# Tweetronic_Base.net
KiCad netlist of a schematic drawn in EAGLE
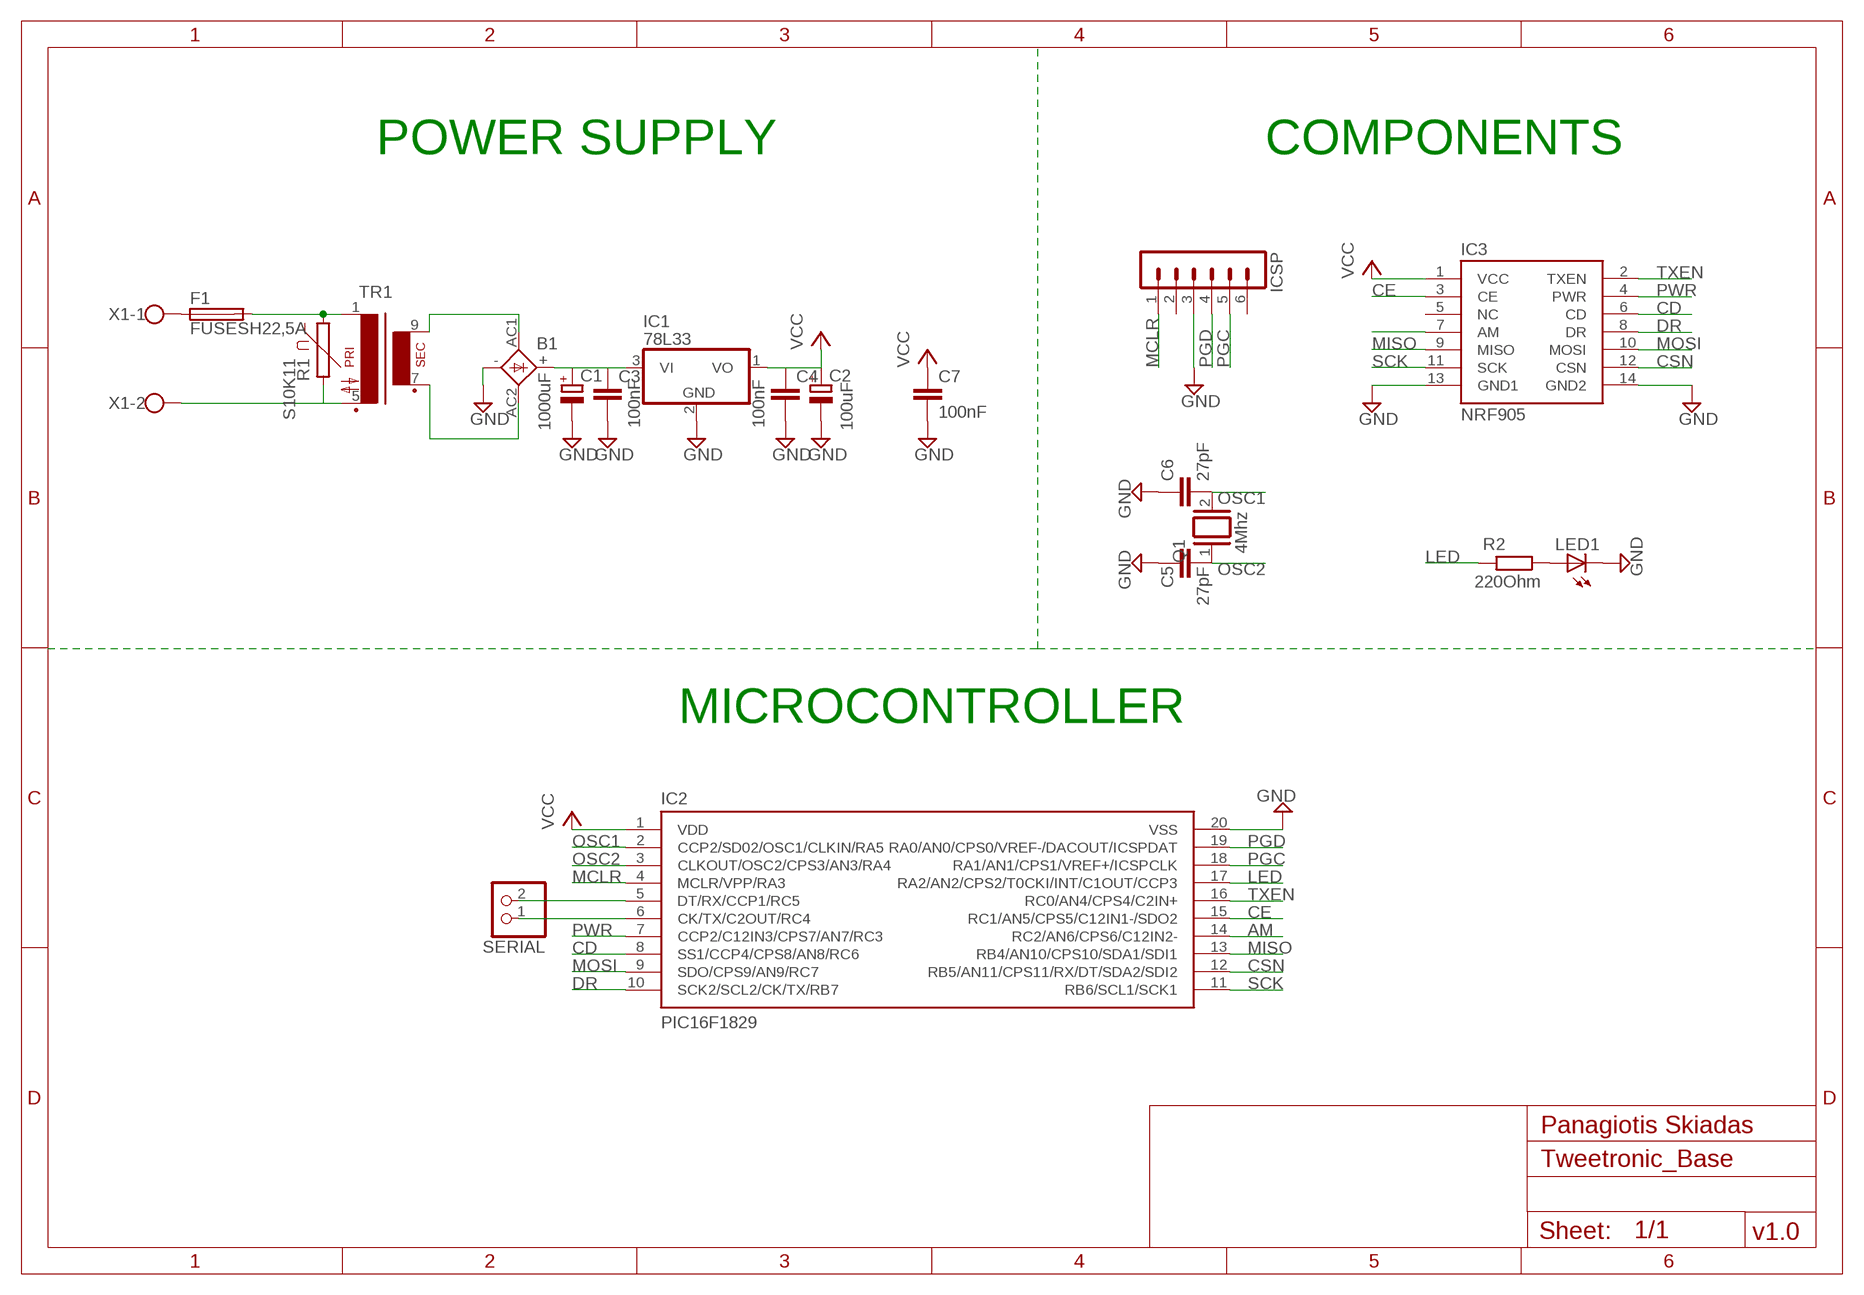
[diagram p0: schematic, sheet 1]

(export (version "E")
  (design (tool "Eeschema 10.0.6"))
  (components
    (comp (ref "B1")
      (value "1KAB")
      (footprint "eagle-import:1KAB")
      (libsource (lib "eagle-import") (part "1KAB"))
    )
    (comp (ref "C1")
      (value "1000uF")
      (footprint "eagle-import:E5-13")
      (libsource (lib "eagle-import") (part "CPOL-EUE5-13"))
    )
    (comp (ref "C2")
      (value "100uF")
      (footprint "eagle-import:E3,5-8")
      (libsource (lib "eagle-import") (part "CPOL-EUE3.5-8"))
    )
    (comp (ref "C3")
      (value "100nF")
      (footprint "eagle-import:C5B3")
      (libsource (lib "eagle-import") (part "C5/3"))
    )
    (comp (ref "C4")
      (value "100nF")
      (footprint "eagle-import:C5B3")
      (libsource (lib "eagle-import") (part "C5/3"))
    )
    (comp (ref "C5")
      (value "27pF")
      (footprint "eagle-import:C2.5-3")
      (libsource (lib "eagle-import") (part "C2,5-3"))
    )
    (comp (ref "C6")
      (value "27pF")
      (footprint "eagle-import:C2.5-3")
      (libsource (lib "eagle-import") (part "C2,5-3"))
    )
    (comp (ref "C7")
      (value "100nF")
      (footprint "eagle-import:C5B3")
      (libsource (lib "eagle-import") (part "C5/3"))
    )
    (comp (ref "F1")
      (value "FUSESH22,5A")
      (footprint "eagle-import:SH22,5A")
      (libsource (lib "eagle-import") (part "FUSESH22,5A"))
    )
    (comp (ref "IC1")
      (value "78L33")
      (footprint "eagle-import:TO92")
      (libsource (lib "eagle-import") (part "78ZL05"))
    )
    (comp (ref "IC2")
      (value "PIC16F1829")
      (footprint "eagle-import:DIL20")
      (libsource (lib "eagle-import") (part "PIC16F1829"))
    )
    (comp (ref "IC3")
      (value "NRF905")
      (footprint "eagle-import:2X07")
      (libsource (lib "eagle-import") (part "NRF905"))
    )
    (comp (ref "ICSP")
      (value "MA06-1")
      (footprint "eagle-import:MA06-1")
      (libsource (lib "eagle-import") (part "MA06-1"))
    )
    (comp (ref "LED1")
      (value "LED5MM")
      (footprint "eagle-import:LED5MM")
      (libsource (lib "eagle-import") (part "LED5MM"))
    )
    (comp (ref "Q1")
      (value "4Mhz")
      (footprint "eagle-import:QS")
      (libsource (lib "eagle-import") (part "XTAL/S"))
    )
    (comp (ref "R1")
      (value "S10K11")
      (footprint "eagle-import:S10K11")
      (libsource (lib "eagle-import") (part "S10K11"))
    )
    (comp (ref "R2")
      (value "220Ohm")
      (footprint "eagle-import:0207_10")
      (libsource (lib "eagle-import") (part "R-EU_0207/10"))
    )
    (comp (ref "SERIAL")
      (value "PINHD-1X2")
      (footprint "eagle-import:1X02")
      (libsource (lib "eagle-import") (part "PINHD-1X2"))
    )
    (comp (ref "TR1")
      (value "VR11")
      (footprint "eagle-import:VR11")
      (libsource (lib "eagle-import") (part "VR11"))
    )
    (comp (ref "X1")
      (value "W237-102")
      (footprint "eagle-import:W237-102")
      (fields (field (name "MPN") "237-102"))
      (libsource (lib "eagle-import") (part "W237-102"))
    )
  )
  (nets
    (net (code "1") (name "/AM") (class "Default")
      (node (ref "IC2") (pin "14") (pinfunction "RC2/AN6/CPS6/C12IN2-_14") (pintype "bidirectional"))
      (node (ref "IC3") (pin "7") (pinfunction "AM_7") (pintype "bidirectional"))
    )
    (net (code "2") (name "/CD") (class "Default")
      (node (ref "IC2") (pin "8") (pinfunction "SS1/CCP4/CPS8/AN8/RC6_8") (pintype "bidirectional"))
      (node (ref "IC3") (pin "6") (pinfunction "CD_6") (pintype "bidirectional"))
    )
    (net (code "3") (name "/CE") (class "Default")
      (node (ref "IC2") (pin "15") (pinfunction "RC1/AN5/CPS5/C12IN1-/SDO2_15") (pintype "bidirectional"))
      (node (ref "IC3") (pin "3") (pinfunction "CE_3") (pintype "bidirectional"))
    )
    (net (code "4") (name "/CSN") (class "Default")
      (node (ref "IC2") (pin "12") (pinfunction "RB5/AN11/CPS11/RX/DT/SDA2/SDI2_12") (pintype "bidirectional"))
      (node (ref "IC3") (pin "12") (pinfunction "CSN_12") (pintype "bidirectional"))
    )
    (net (code "5") (name "/DR") (class "Default")
      (node (ref "IC2") (pin "10") (pinfunction "SCK2/SCL2/CK/TX/RB7_10") (pintype "bidirectional"))
      (node (ref "IC3") (pin "8") (pinfunction "DR_8") (pintype "bidirectional"))
    )
    (net (code "6") (name "/LED") (class "Default")
      (node (ref "IC2") (pin "17") (pinfunction "RA2/AN2/CPS2/T0CKI/INT/C1OUT/CCP3_17") (pintype "bidirectional"))
      (node (ref "R2") (pin "2") (pinfunction "2_2") (pintype "passive"))
    )
    (net (code "7") (name "/MCLR") (class "Default")
      (node (ref "IC2") (pin "4") (pinfunction "MCLR/VPP/RA3_4") (pintype "bidirectional"))
      (node (ref "ICSP") (pin "1") (pinfunction "1_1") (pintype "passive"))
    )
    (net (code "8") (name "/MISO") (class "Default")
      (node (ref "IC2") (pin "13") (pinfunction "RB4/AN10/CPS10/SDA1/SDI1_13") (pintype "bidirectional"))
      (node (ref "IC3") (pin "9") (pinfunction "MISO_9") (pintype "bidirectional"))
    )
    (net (code "9") (name "/MOSI") (class "Default")
      (node (ref "IC2") (pin "9") (pinfunction "SDO/CPS9/AN9/RC7_9") (pintype "bidirectional"))
      (node (ref "IC3") (pin "10") (pinfunction "MOSI_10") (pintype "bidirectional"))
    )
    (net (code "10") (name "/OSC1") (class "Default")
      (node (ref "C6") (pin "2") (pinfunction "2_2") (pintype "passive"))
      (node (ref "IC2") (pin "2") (pinfunction "CCP2/SD02/OSC1/CLKIN/RA5_2") (pintype "bidirectional"))
      (node (ref "Q1") (pin "2") (pinfunction "2_2") (pintype "passive"))
    )
    (net (code "11") (name "/OSC2") (class "Default")
      (node (ref "C5") (pin "2") (pinfunction "2_2") (pintype "passive"))
      (node (ref "IC2") (pin "3") (pinfunction "CLKOUT/OSC2/CPS3/AN3/RA4_3") (pintype "bidirectional"))
      (node (ref "Q1") (pin "1") (pinfunction "1_1") (pintype "passive"))
    )
    (net (code "12") (name "/PGC") (class "Default")
      (node (ref "IC2") (pin "18") (pinfunction "RA1/AN1/CPS1/VREF+/ICSPCLK_18") (pintype "bidirectional"))
      (node (ref "ICSP") (pin "5") (pinfunction "5_5") (pintype "passive"))
    )
    (net (code "13") (name "/PGD") (class "Default")
      (node (ref "IC2") (pin "19") (pinfunction "RA0/AN0/CPS0/VREF-/DACOUT/ICSPDAT_19") (pintype "bidirectional"))
      (node (ref "ICSP") (pin "4") (pinfunction "4_4") (pintype "passive"))
    )
    (net (code "14") (name "/PWR") (class "Default")
      (node (ref "IC2") (pin "7") (pinfunction "CCP2/C12IN3/CPS7/AN7/RC3_7") (pintype "bidirectional"))
      (node (ref "IC3") (pin "4") (pinfunction "PWR_4") (pintype "bidirectional"))
    )
    (net (code "15") (name "/SCK") (class "Default")
      (node (ref "IC2") (pin "11") (pinfunction "RB6/SCL1/SCK1_11") (pintype "bidirectional"))
      (node (ref "IC3") (pin "11") (pinfunction "SCK_11") (pintype "bidirectional"))
    )
    (net (code "16") (name "/TXEN") (class "Default")
      (node (ref "IC2") (pin "16") (pinfunction "RC0/AN4/CPS4/C2IN+_16") (pintype "bidirectional"))
      (node (ref "IC3") (pin "2") (pinfunction "TXEN_2") (pintype "bidirectional"))
    )
    (net (code "17") (name "GND") (class "Default")
      (node (ref "B1") (pin "-") (pinfunction "-_-") (pintype "passive"))
      (node (ref "C1") (pin "-") (pinfunction "-_-") (pintype "passive"))
      (node (ref "C2") (pin "-") (pinfunction "-_-") (pintype "passive"))
      (node (ref "C3") (pin "2") (pinfunction "2_2") (pintype "passive"))
      (node (ref "C4") (pin "2") (pinfunction "2_2") (pintype "passive"))
      (node (ref "C5") (pin "1") (pinfunction "1_1") (pintype "passive"))
      (node (ref "C6") (pin "1") (pinfunction "1_1") (pintype "passive"))
      (node (ref "C7") (pin "2") (pinfunction "2_2") (pintype "passive"))
      (node (ref "IC1") (pin "2") (pinfunction "GND_2") (pintype "passive"))
      (node (ref "IC2") (pin "20") (pinfunction "VSS_20") (pintype "bidirectional"))
      (node (ref "IC3") (pin "13") (pinfunction "GND1_13") (pintype "bidirectional"))
      (node (ref "IC3") (pin "14") (pinfunction "GND2_14") (pintype "bidirectional"))
      (node (ref "ICSP") (pin "3") (pinfunction "3_3") (pintype "passive"))
      (node (ref "LED1") (pin "K") (pinfunction "C_K") (pintype "passive"))
    )
    (net (code "18") (name "Net-(IC1-VI)") (class "Default")
      (node (ref "B1") (pin "+") (pinfunction "+_+") (pintype "passive"))
      (node (ref "C1") (pin "+") (pinfunction "+_+") (pintype "passive"))
      (node (ref "C3") (pin "1") (pinfunction "1_1") (pintype "passive"))
      (node (ref "IC1") (pin "3") (pinfunction "VI_3") (pintype "input"))
    )
    (net (code "19") (name "Net-(IC2-CK{slash}TX{slash}C2OUT{slash}RC4)") (class "Default")
      (node (ref "IC2") (pin "6") (pinfunction "CK/TX/C2OUT/RC4_6") (pintype "bidirectional"))
      (node (ref "SERIAL") (pin "1") (pinfunction "1_1") (pintype "passive"))
    )
    (net (code "20") (name "Net-(IC2-DT{slash}RX{slash}CCP1{slash}RC5)") (class "Default")
      (node (ref "IC2") (pin "5") (pinfunction "DT/RX/CCP1/RC5_5") (pintype "bidirectional"))
      (node (ref "SERIAL") (pin "2") (pinfunction "2_2") (pintype "passive"))
    )
    (net (code "21") (name "Net-(LED1-PadA)") (class "Default")
      (node (ref "LED1") (pin "A") (pinfunction "A_A") (pintype "passive"))
      (node (ref "R2") (pin "1") (pinfunction "1_1") (pintype "passive"))
    )
    (net (code "22") (name "Net-(TR1-P1)") (class "Default")
      (node (ref "F1") (pin "2") (pinfunction "2_2") (pintype "passive"))
      (node (ref "R1") (pin "1") (pinfunction "1_1") (pintype "passive"))
      (node (ref "TR1") (pin "1") (pinfunction "P1_1") (pintype "passive"))
    )
    (net (code "23") (name "Net-(TR1-P2)") (class "Default")
      (node (ref "R1") (pin "2") (pinfunction "2_2") (pintype "passive"))
      (node (ref "TR1") (pin "5") (pinfunction "P2_5") (pintype "passive"))
      (node (ref "X1") (pin "2") (pinfunction "KL_2") (pintype "passive"))
    )
    (net (code "24") (name "Net-(TR1-S3)") (class "Default")
      (node (ref "B1") (pin "AC2") (pinfunction "AC2_AC2") (pintype "passive"))
      (node (ref "TR1") (pin "7") (pinfunction "S3_7") (pintype "passive"))
    )
    (net (code "25") (name "Net-(TR1-S4)") (class "Default")
      (node (ref "B1") (pin "AC1") (pinfunction "AC1_AC1") (pintype "passive"))
      (node (ref "TR1") (pin "9") (pinfunction "S4_9") (pintype "passive"))
    )
    (net (code "26") (name "Net-(X1A-KL)") (class "Default")
      (node (ref "F1") (pin "1") (pinfunction "1_1") (pintype "passive"))
      (node (ref "X1") (pin "1") (pinfunction "KL_1") (pintype "passive"))
    )
    (net (code "27") (name "VCC") (class "Default")
      (node (ref "C2") (pin "+") (pinfunction "+_+") (pintype "passive"))
      (node (ref "C4") (pin "1") (pinfunction "1_1") (pintype "passive"))
      (node (ref "C7") (pin "1") (pinfunction "1_1") (pintype "passive"))
      (node (ref "IC1") (pin "1") (pinfunction "VO_1") (pintype "passive"))
      (node (ref "IC2") (pin "1") (pinfunction "VDD_1") (pintype "bidirectional"))
      (node (ref "IC3") (pin "1") (pinfunction "VCC_1") (pintype "bidirectional"))
    )
    (net (code "28") (name "unconnected-(IC3-NC-Pad5)") (class "Default")
      (node (ref "IC3") (pin "5") (pinfunction "NC_5") (pintype "bidirectional"))
    )
    (net (code "29") (name "unconnected-(ICSP-Pad2)") (class "Default")
      (node (ref "ICSP") (pin "2") (pinfunction "2_2") (pintype "passive"))
    )
    (net (code "30") (name "unconnected-(ICSP-Pad6)") (class "Default")
      (node (ref "ICSP") (pin "6") (pinfunction "6_6") (pintype "passive"))
    )
  )
)
